# POWER_REG.net
KiCad netlist of a schematic drawn in Altium Designer
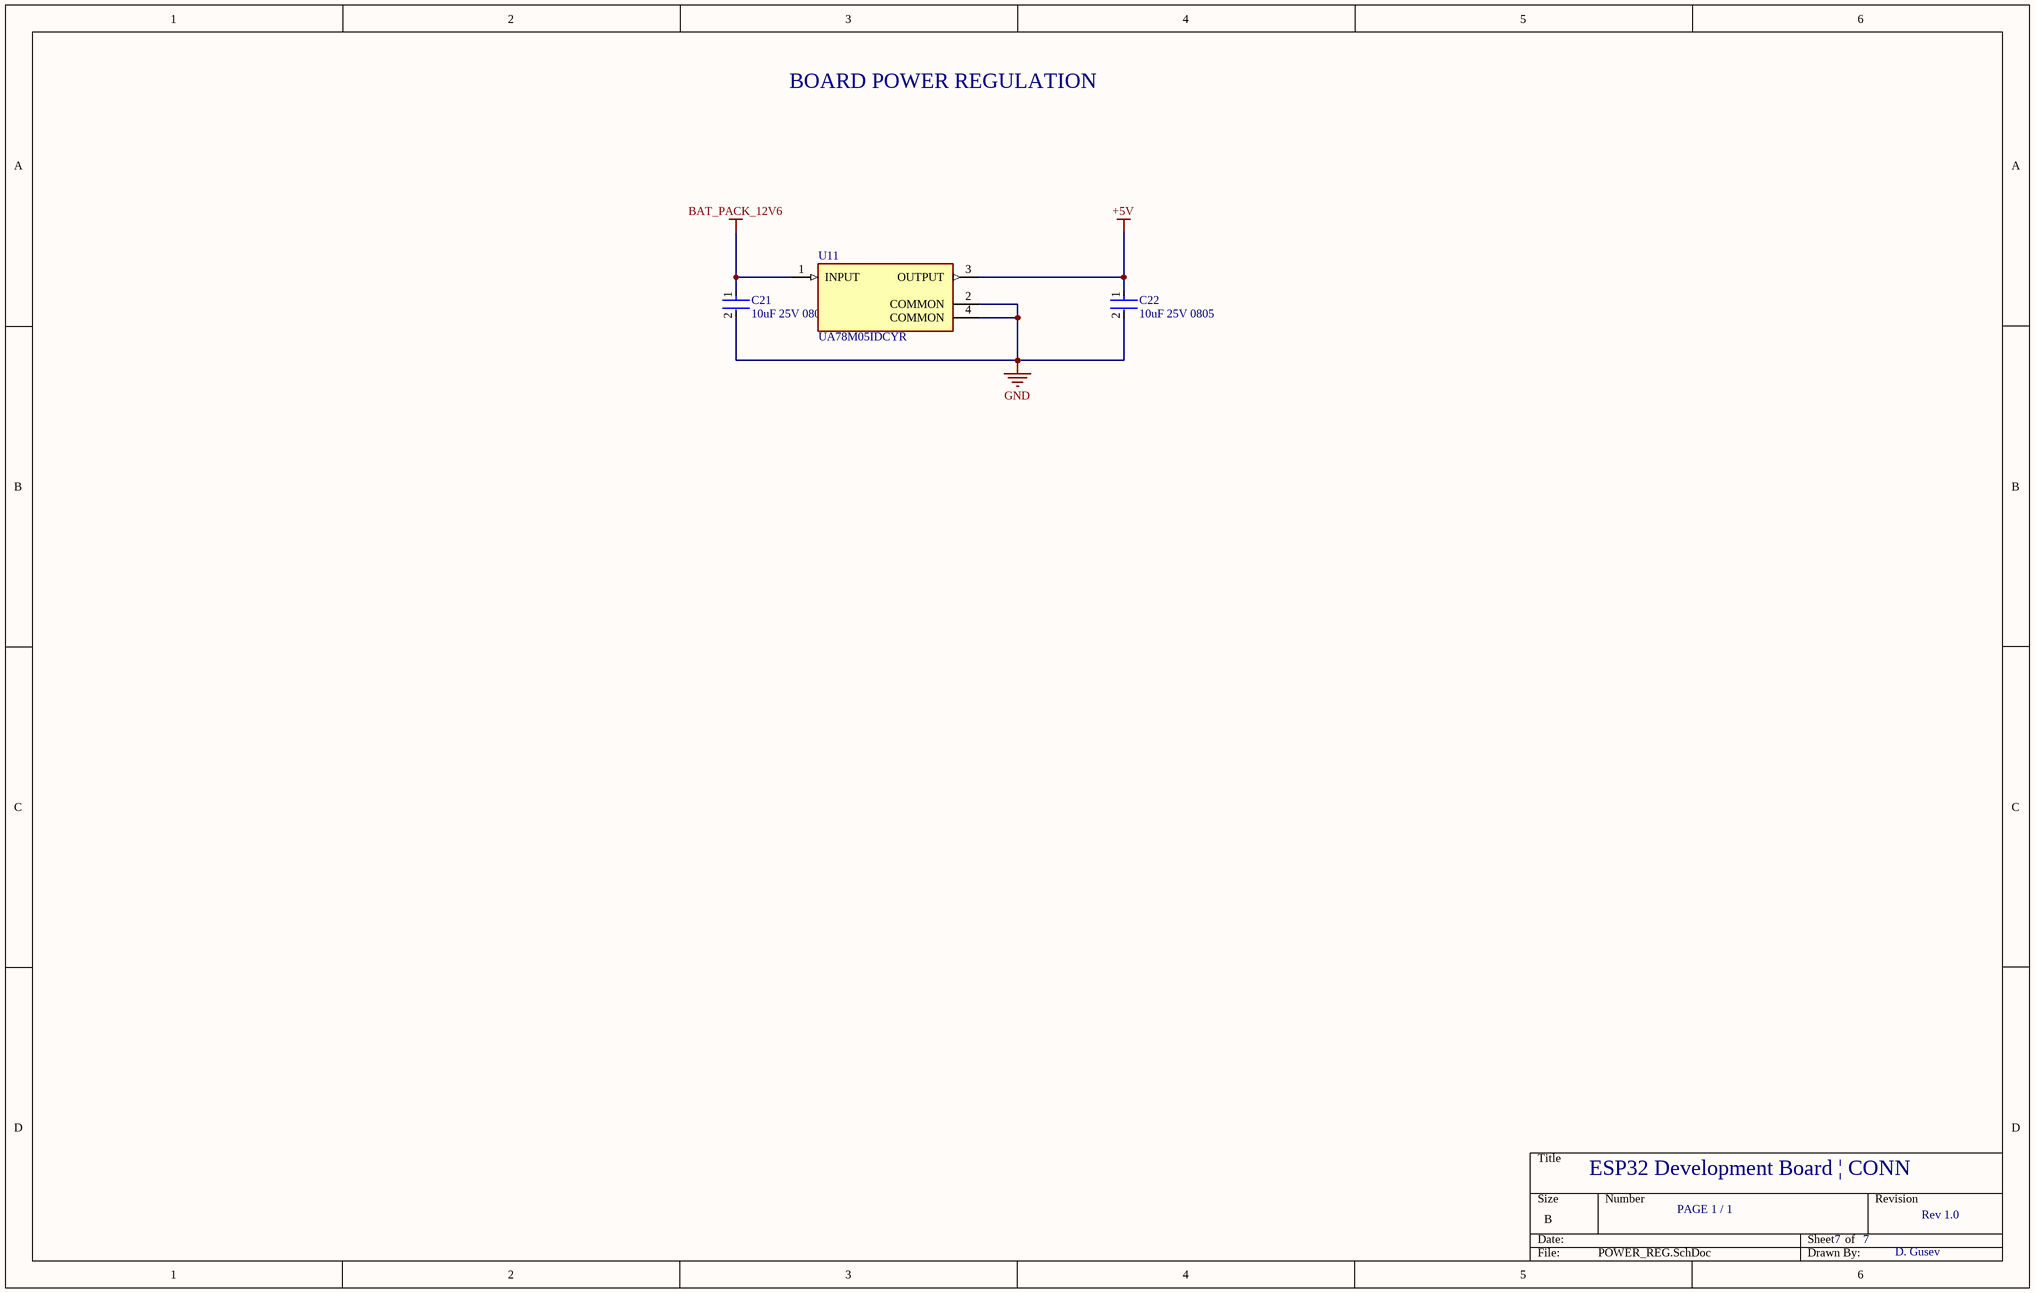
[diagram p0: POWER_REG.SchDoc]

(export (version "E")
  (design (tool "Eeschema 10.0.6"))
  (components
    (comp (ref "C21")
      (value "10uF 25V 0805")
      (footprint "FP-GRM21B-0_15-IPC_C")
      (description "Chip Multilayer Ceramic Capacitors for General Purpose, 0805, 10uF, X5R, 15%, 10%, 25V")
      (fields (field (name "VOLTAGE") "25V") (field (name "TOLERANCE") "10%"))
      (libsource (lib "Altium Content Vault") (part "b4654b650e69147ec39a6b967a45e02"))
    )
    (comp (ref "C22")
      (value "10uF 25V 0805")
      (footprint "FP-GRM21B-0_15-IPC_C")
      (description "Chip Multilayer Ceramic Capacitors for General Purpose, 0805, 10uF, X5R, 15%, 10%, 25V")
      (fields (field (name "VOLTAGE") "25V") (field (name "TOLERANCE") "10%"))
      (libsource (lib "Altium Content Vault") (part "b4654b650e69147ec39a6b967a45e02"))
    )
    (comp (ref "U11")
      (value "UA78M05IDCYR")
      (footprint "FP-DCY0004A-MFG")
      (description "IC REG LINEAR 5V 500MA SOT223-4")
      (fields
        (field (name "OCTOPART") "https://octopart.com/ua78m05idcyr-texas+instruments-525575")
        (field (name "MANUFACTURER") "Texas Instruments")
      )
      (libsource (lib "Altium Content Vault") (part "8ae96a6a62262bf838d5da5965c01e6"))
    )
  )
  (nets
    (net (code "1") (name "+5V") (class "Default")
      (node (ref "C22") (pin "1") (pinfunction "1_1") (pintype "passive"))
      (node (ref "U11") (pin "3") (pinfunction "OUTPUT_3") (pintype "output"))
    )
    (net (code "2") (name "BAT_PACK_12V6") (class "Default")
      (node (ref "C21") (pin "1") (pinfunction "1_1") (pintype "passive"))
      (node (ref "U11") (pin "1") (pinfunction "INPUT_1") (pintype "input"))
    )
    (net (code "3") (name "GND") (class "Default")
      (node (ref "C21") (pin "2") (pinfunction "2_2") (pintype "passive"))
      (node (ref "C22") (pin "2") (pinfunction "2_2") (pintype "passive"))
      (node (ref "U11") (pin "2") (pinfunction "COMMON_2") (pintype "passive"))
      (node (ref "U11") (pin "4") (pinfunction "COMMON_4") (pintype "passive"))
    )
  )
)
